# Tarjeta4.net
KiCad netlist of a schematic drawn in EAGLE
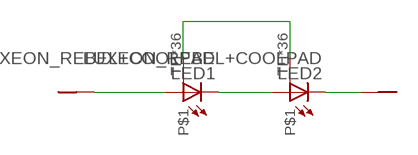
[diagram p0: schematic, sheet 1]

(export (version "E")
  (design (tool "Eeschema 10.0.6"))
  (components
    (comp (ref "LED1")
      (value "LUXEON_REBEL+COOLPAD")
      (footprint "eagle-import:LUXEON_REBEL+COOLPAD")
      (libsource (lib "eagle-import") (part "LUXEON_REBEL+COOLPAD"))
    )
    (comp (ref "LED2")
      (value "LUXEON_REBEL+COOLPAD")
      (footprint "eagle-import:LUXEON_REBEL+COOLPAD")
      (libsource (lib "eagle-import") (part "LUXEON_REBEL+COOLPAD"))
    )
    (comp (ref "U$1")
      (value "POWER_PIN")
      (footprint "eagle-import:POWER_PIN")
      (libsource (lib "eagle-import") (part "POWER_PIN"))
    )
    (comp (ref "U$2")
      (value "POWER_PIN")
      (footprint "eagle-import:POWER_PIN")
      (libsource (lib "eagle-import") (part "POWER_PIN"))
    )
  )
  (nets
    (net (code "1") (name "Net-(LED1-A-PadA@1)") (class "Default")
      (node (ref "LED1") (pin "A") (pinfunction "A_A") (pintype "passive"))
      (node (ref "LED1") (pin "A@1") (pinfunction "A_A@1") (pintype "passive"))
      (node (ref "U$1") (pin "P$1") (pinfunction "P$1_P$1") (pintype "bidirectional"))
    )
    (net (code "2") (name "Net-(LED1-C-PadC@1)") (class "Default")
      (node (ref "LED1") (pin "C") (pinfunction "C_C") (pintype "passive"))
      (node (ref "LED1") (pin "C@1") (pinfunction "C_C@1") (pintype "passive"))
      (node (ref "LED2") (pin "A") (pinfunction "A_A") (pintype "passive"))
      (node (ref "LED2") (pin "A@1") (pinfunction "A_A@1") (pintype "passive"))
    )
    (net (code "3") (name "Net-(LED1-P$1-PadTH)") (class "Default")
      (node (ref "LED1") (pin "TH") (pinfunction "P$1_TH") (pintype "bidirectional"))
      (node (ref "LED1") (pin "TH@1") (pinfunction "P$1_TH@1") (pintype "bidirectional"))
      (node (ref "LED1") (pin "TH@10") (pinfunction "P$1_TH@10") (pintype "bidirectional"))
      (node (ref "LED1") (pin "TH@11") (pinfunction "P$1_TH@11") (pintype "bidirectional"))
      (node (ref "LED1") (pin "TH@12") (pinfunction "P$1_TH@12") (pintype "bidirectional"))
      (node (ref "LED1") (pin "TH@13") (pinfunction "P$1_TH@13") (pintype "bidirectional"))
      (node (ref "LED1") (pin "TH@14") (pinfunction "P$1_TH@14") (pintype "bidirectional"))
      (node (ref "LED1") (pin "TH@15") (pinfunction "P$1_TH@15") (pintype "bidirectional"))
      (node (ref "LED1") (pin "TH@16") (pinfunction "P$1_TH@16") (pintype "bidirectional"))
      (node (ref "LED1") (pin "TH@17") (pinfunction "P$1_TH@17") (pintype "bidirectional"))
      (node (ref "LED1") (pin "TH@18") (pinfunction "P$1_TH@18") (pintype "bidirectional"))
      (node (ref "LED1") (pin "TH@19") (pinfunction "P$1_TH@19") (pintype "bidirectional"))
      (node (ref "LED1") (pin "TH@2") (pinfunction "P$1_TH@2") (pintype "bidirectional"))
      (node (ref "LED1") (pin "TH@20") (pinfunction "P$1_TH@20") (pintype "bidirectional"))
      (node (ref "LED1") (pin "TH@21") (pinfunction "P$1_TH@21") (pintype "bidirectional"))
      (node (ref "LED1") (pin "TH@22") (pinfunction "P$1_TH@22") (pintype "bidirectional"))
      (node (ref "LED1") (pin "TH@23") (pinfunction "P$1_TH@23") (pintype "bidirectional"))
      (node (ref "LED1") (pin "TH@24") (pinfunction "P$1_TH@24") (pintype "bidirectional"))
      (node (ref "LED1") (pin "TH@25") (pinfunction "P$1_TH@25") (pintype "bidirectional"))
      (node (ref "LED1") (pin "TH@26") (pinfunction "P$1_TH@26") (pintype "bidirectional"))
      (node (ref "LED1") (pin "TH@27") (pinfunction "P$1_TH@27") (pintype "bidirectional"))
      (node (ref "LED1") (pin "TH@28") (pinfunction "P$1_TH@28") (pintype "bidirectional"))
      (node (ref "LED1") (pin "TH@29") (pinfunction "P$1_TH@29") (pintype "bidirectional"))
      (node (ref "LED1") (pin "TH@3") (pinfunction "P$1_TH@3") (pintype "bidirectional"))
      (node (ref "LED1") (pin "TH@30") (pinfunction "P$1_TH@30") (pintype "bidirectional"))
      (node (ref "LED1") (pin "TH@31") (pinfunction "P$1_TH@31") (pintype "bidirectional"))
      (node (ref "LED1") (pin "TH@32") (pinfunction "P$1_TH@32") (pintype "bidirectional"))
      (node (ref "LED1") (pin "TH@33") (pinfunction "P$1_TH@33") (pintype "bidirectional"))
      (node (ref "LED1") (pin "TH@34") (pinfunction "P$1_TH@34") (pintype "bidirectional"))
      (node (ref "LED1") (pin "TH@35") (pinfunction "P$1_TH@35") (pintype "bidirectional"))
      (node (ref "LED1") (pin "TH@4") (pinfunction "P$1_TH@4") (pintype "bidirectional"))
      (node (ref "LED1") (pin "TH@5") (pinfunction "P$1_TH@5") (pintype "bidirectional"))
      (node (ref "LED1") (pin "TH@6") (pinfunction "P$1_TH@6") (pintype "bidirectional"))
      (node (ref "LED1") (pin "TH@7") (pinfunction "P$1_TH@7") (pintype "bidirectional"))
      (node (ref "LED1") (pin "TH@8") (pinfunction "P$1_TH@8") (pintype "bidirectional"))
      (node (ref "LED1") (pin "TH@9") (pinfunction "P$1_TH@9") (pintype "bidirectional"))
      (node (ref "LED2") (pin "TH") (pinfunction "P$1_TH") (pintype "bidirectional"))
      (node (ref "LED2") (pin "TH@1") (pinfunction "P$1_TH@1") (pintype "bidirectional"))
      (node (ref "LED2") (pin "TH@10") (pinfunction "P$1_TH@10") (pintype "bidirectional"))
      (node (ref "LED2") (pin "TH@11") (pinfunction "P$1_TH@11") (pintype "bidirectional"))
      (node (ref "LED2") (pin "TH@12") (pinfunction "P$1_TH@12") (pintype "bidirectional"))
      (node (ref "LED2") (pin "TH@13") (pinfunction "P$1_TH@13") (pintype "bidirectional"))
      (node (ref "LED2") (pin "TH@14") (pinfunction "P$1_TH@14") (pintype "bidirectional"))
      (node (ref "LED2") (pin "TH@15") (pinfunction "P$1_TH@15") (pintype "bidirectional"))
      (node (ref "LED2") (pin "TH@16") (pinfunction "P$1_TH@16") (pintype "bidirectional"))
      (node (ref "LED2") (pin "TH@17") (pinfunction "P$1_TH@17") (pintype "bidirectional"))
      (node (ref "LED2") (pin "TH@18") (pinfunction "P$1_TH@18") (pintype "bidirectional"))
      (node (ref "LED2") (pin "TH@19") (pinfunction "P$1_TH@19") (pintype "bidirectional"))
      (node (ref "LED2") (pin "TH@2") (pinfunction "P$1_TH@2") (pintype "bidirectional"))
      (node (ref "LED2") (pin "TH@20") (pinfunction "P$1_TH@20") (pintype "bidirectional"))
      (node (ref "LED2") (pin "TH@21") (pinfunction "P$1_TH@21") (pintype "bidirectional"))
      (node (ref "LED2") (pin "TH@22") (pinfunction "P$1_TH@22") (pintype "bidirectional"))
      (node (ref "LED2") (pin "TH@23") (pinfunction "P$1_TH@23") (pintype "bidirectional"))
      (node (ref "LED2") (pin "TH@24") (pinfunction "P$1_TH@24") (pintype "bidirectional"))
      (node (ref "LED2") (pin "TH@25") (pinfunction "P$1_TH@25") (pintype "bidirectional"))
      (node (ref "LED2") (pin "TH@26") (pinfunction "P$1_TH@26") (pintype "bidirectional"))
      (node (ref "LED2") (pin "TH@27") (pinfunction "P$1_TH@27") (pintype "bidirectional"))
      (node (ref "LED2") (pin "TH@28") (pinfunction "P$1_TH@28") (pintype "bidirectional"))
      (node (ref "LED2") (pin "TH@29") (pinfunction "P$1_TH@29") (pintype "bidirectional"))
      (node (ref "LED2") (pin "TH@3") (pinfunction "P$1_TH@3") (pintype "bidirectional"))
      (node (ref "LED2") (pin "TH@30") (pinfunction "P$1_TH@30") (pintype "bidirectional"))
      (node (ref "LED2") (pin "TH@31") (pinfunction "P$1_TH@31") (pintype "bidirectional"))
      (node (ref "LED2") (pin "TH@32") (pinfunction "P$1_TH@32") (pintype "bidirectional"))
      (node (ref "LED2") (pin "TH@33") (pinfunction "P$1_TH@33") (pintype "bidirectional"))
      (node (ref "LED2") (pin "TH@34") (pinfunction "P$1_TH@34") (pintype "bidirectional"))
      (node (ref "LED2") (pin "TH@35") (pinfunction "P$1_TH@35") (pintype "bidirectional"))
      (node (ref "LED2") (pin "TH@4") (pinfunction "P$1_TH@4") (pintype "bidirectional"))
      (node (ref "LED2") (pin "TH@5") (pinfunction "P$1_TH@5") (pintype "bidirectional"))
      (node (ref "LED2") (pin "TH@6") (pinfunction "P$1_TH@6") (pintype "bidirectional"))
      (node (ref "LED2") (pin "TH@7") (pinfunction "P$1_TH@7") (pintype "bidirectional"))
      (node (ref "LED2") (pin "TH@8") (pinfunction "P$1_TH@8") (pintype "bidirectional"))
      (node (ref "LED2") (pin "TH@9") (pinfunction "P$1_TH@9") (pintype "bidirectional"))
    )
    (net (code "4") (name "Net-(LED2-C-PadC@1)") (class "Default")
      (node (ref "LED2") (pin "C") (pinfunction "C_C") (pintype "passive"))
      (node (ref "LED2") (pin "C@1") (pinfunction "C_C@1") (pintype "passive"))
      (node (ref "U$2") (pin "P$1") (pinfunction "P$1_P$1") (pintype "bidirectional"))
    )
  )
)
